# Light_Sensor_Breakout.net
KiCad netlist of a schematic drawn in Altium Designer
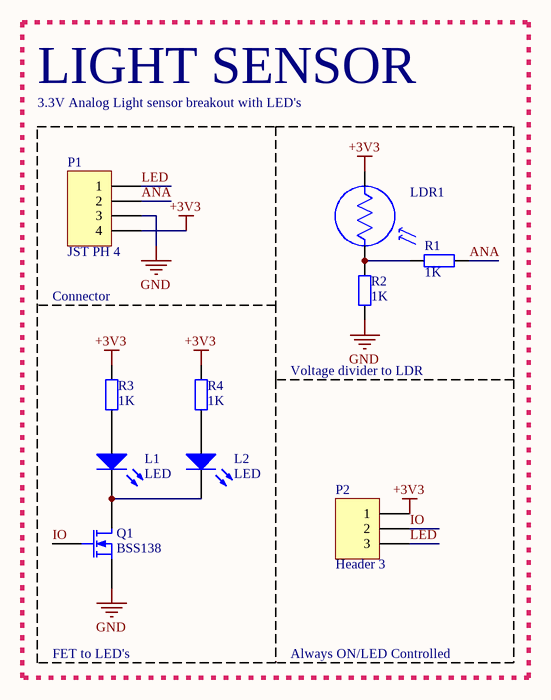
[diagram p0: Light Sensor Breakout.SchDoc]

(export (version "E")
  (design (tool "Eeschema 10.0.6"))
  (components
    (comp (ref "L1") (value "LED") (footprint "LED-5mm") (libsource (lib "CustomLibrary") (part "LED")))
    (comp (ref "L2") (value "LED") (footprint "LED-5mm") (libsource (lib "CustomLibrary") (part "LED")))
    (comp (ref "LDR1") (value "LDR") (footprint "LDR-5mm") (libsource (lib "CustomLibrary") (part "LDR")))
    (comp (ref "P1")
      (value "JST PH 4")
      (footprint "B4B-PH-K")
      (libsource (lib "CustomLibrary") (part "JST PH 4"))
    )
    (comp (ref "P2")
      (value "Header 3")
      (footprint "HDR1X3")
      (description "Header, 3-Pin")
      (fields (field (name "PUBLISHER") "Altium Limited"))
      (libsource (lib "Miscellaneous Connectors") (part "Header 3"))
    )
    (comp (ref "Q1")
      (value "BSS138")
      (footprint "SOT23")
      (description "N-Channel Enhancement Mode Vertical DMOS FET")
      (fields (field (name "PUBLISHER") "Altium Limited"))
      (libsource (lib "Zetex Discrete MOSFET") (part "BSS138"))
    )
    (comp (ref "R1") (value "1K") (footprint "RES1206") (libsource (lib "CustomLibrary") (part "RES")))
    (comp (ref "R2") (value "1K") (footprint "RES1206") (libsource (lib "") (part "RES_1")))
    (comp (ref "R3") (value "1K") (footprint "RES1206") (libsource (lib "") (part "RES_1")))
    (comp (ref "R4") (value "1K") (footprint "RES1206") (libsource (lib "") (part "RES_1")))
  )
  (nets
    (net (code "1") (name "+3V3") (class "Default")
      (node (ref "LDR1") (pin "1") (pinfunction "1_1") (pintype "passive"))
      (node (ref "P1") (pin "4") (pinfunction "4_4") (pintype "passive"))
      (node (ref "P2") (pin "1") (pinfunction "1_1") (pintype "passive"))
      (node (ref "R3") (pin "2") (pinfunction "2_2") (pintype "passive"))
      (node (ref "R4") (pin "2") (pinfunction "2_2") (pintype "passive"))
    )
    (net (code "2") (name "/ANA") (class "Default")
      (node (ref "P1") (pin "2") (pinfunction "2_2") (pintype "passive"))
      (node (ref "R1") (pin "1") (pinfunction "1_1") (pintype "passive"))
    )
    (net (code "3") (name "/IO") (class "Default")
      (node (ref "P2") (pin "2") (pinfunction "2_2") (pintype "passive"))
      (node (ref "Q1") (pin "3") (pinfunction "G_3") (pintype "passive"))
    )
    (net (code "4") (name "/LED") (class "Default")
      (node (ref "P1") (pin "1") (pinfunction "1_1") (pintype "passive"))
      (node (ref "P2") (pin "3") (pinfunction "3_3") (pintype "passive"))
    )
    (net (code "5") (name "GND") (class "Default")
      (node (ref "P1") (pin "3") (pinfunction "3_3") (pintype "passive"))
      (node (ref "Q1") (pin "2") (pinfunction "S_2") (pintype "passive"))
      (node (ref "R2") (pin "1") (pinfunction "1_1") (pintype "passive"))
    )
    (net (code "6") (name "Net-(L1-A)") (class "Default")
      (node (ref "L1") (pin "1") (pinfunction "A_1") (pintype "passive"))
      (node (ref "R3") (pin "1") (pinfunction "1_1") (pintype "passive"))
    )
    (net (code "7") (name "Net-(L1-K)") (class "Default")
      (node (ref "L1") (pin "2") (pinfunction "K_2") (pintype "passive"))
      (node (ref "L2") (pin "2") (pinfunction "K_2") (pintype "passive"))
      (node (ref "Q1") (pin "1") (pinfunction "D_1") (pintype "passive"))
    )
    (net (code "8") (name "Net-(L2-A)") (class "Default")
      (node (ref "L2") (pin "1") (pinfunction "A_1") (pintype "passive"))
      (node (ref "R4") (pin "1") (pinfunction "1_1") (pintype "passive"))
    )
    (net (code "9") (name "Net-(LDR1-Pad2)") (class "Default")
      (node (ref "LDR1") (pin "2") (pinfunction "2_2") (pintype "passive"))
      (node (ref "R1") (pin "2") (pinfunction "2_2") (pintype "passive"))
      (node (ref "R2") (pin "2") (pinfunction "2_2") (pintype "passive"))
    )
  )
)
